# CH552DAPLINK.net
KiCad netlist of a schematic drawn in Altium Designer
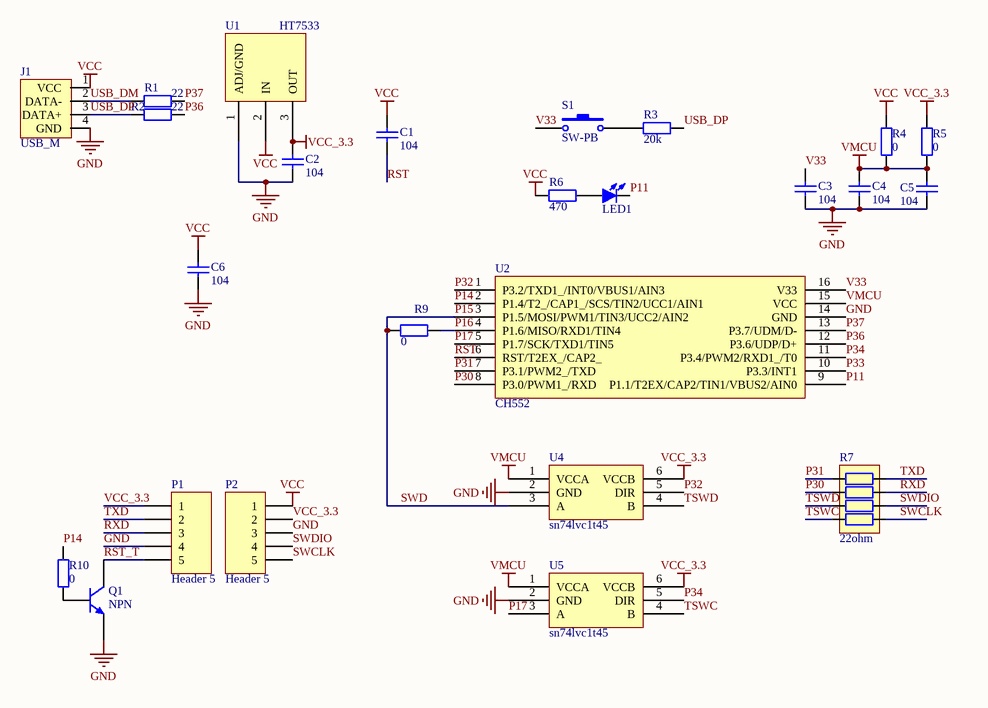
[diagram p0: CH552DAPLINK.SchDoc]

(export (version "E")
  (design (tool "Eeschema 10.0.6"))
  (components
    (comp (ref "C1")
      (value "104")
      (footprint "MY0603_c")
      (description "Capacitor")
      (fields (field (name "Comment") "Cap") (field (name "PUBLISHER") "Altium Limited"))
      (libsource (lib "Miscellaneous Devices") (part "Cap"))
    )
    (comp (ref "C2")
      (value "104")
      (footprint "MY0805_C")
      (description "Capacitor")
      (fields (field (name "Comment") "Cap") (field (name "PUBLISHER") "Altium Limited"))
      (libsource (lib "Miscellaneous Devices") (part "Cap"))
    )
    (comp (ref "C3")
      (value "104")
      (footprint "MY0805_C")
      (description "Capacitor")
      (fields (field (name "Comment") "Cap") (field (name "PUBLISHER") "Altium Limited"))
      (libsource (lib "Miscellaneous Devices") (part "Cap"))
    )
    (comp (ref "C4")
      (value "104")
      (footprint "MY0603_c")
      (description "Capacitor")
      (fields (field (name "Comment") "Cap") (field (name "PUBLISHER") "Altium Limited"))
      (libsource (lib "Miscellaneous Devices") (part "Cap"))
    )
    (comp (ref "C5")
      (value "104")
      (footprint "MY0805_C")
      (description "Capacitor")
      (fields (field (name "Comment") "Cap") (field (name "PUBLISHER") "Altium Limited"))
      (libsource (lib "Miscellaneous Devices") (part "Cap"))
    )
    (comp (ref "C6")
      (value "104")
      (footprint "MY0805_C")
      (description "Capacitor")
      (fields (field (name "Comment") "Cap") (field (name "PUBLISHER") "Altium Limited"))
      (libsource (lib "Miscellaneous Devices") (part "Cap"))
    )
    (comp (ref "J1") (value "USB_M") (footprint "USB_micro_常用") (libsource (lib "SCH封装库") (part "USB_M")))
    (comp (ref "LED1")
      (value "LED-SMD")
      (footprint "MY-0603_LED_B")
      (description "贴片LED")
      (libsource (lib "MY LIB") (part "LED-SMD"))
    )
    (comp (ref "P1")
      (value "Header 5")
      (footprint "header5")
      (description "Header, 5-Pin")
      (fields (field (name "PUBLISHER") "Altium Limited"))
      (libsource (lib "Miscellaneous Connectors") (part "Header 5"))
    )
    (comp (ref "P2")
      (value "Header 5")
      (footprint "header5")
      (description "Header, 5-Pin")
      (fields (field (name "PUBLISHER") "Altium Limited"))
      (libsource (lib "") (part "Header 5_1"))
    )
    (comp (ref "Q1")
      (value "NPN")
      (footprint "MY_SOT23_BJT")
      (description "NPN Bipolar Transistor")
      (fields (field (name "PUBLISHER") "Altium Limited"))
      (libsource (lib "MY BJT&MOS") (part "NPN_SOT23"))
    )
    (comp (ref "R1")
      (value "22")
      (footprint "my0603_R")
      (description "Resistor")
      (fields (field (name "Comment") "Res2") (field (name "PUBLISHER") "Altium Limited"))
      (libsource (lib "") (part "Res2_1"))
    )
    (comp (ref "R2")
      (value "22")
      (footprint "my0603_R")
      (description "Resistor")
      (fields (field (name "Comment") "Res2") (field (name "PUBLISHER") "Altium Limited"))
      (libsource (lib "") (part "Res2_1"))
    )
    (comp (ref "R3")
      (value "20k")
      (footprint "my0603_r")
      (description "Resistor")
      (fields (field (name "Comment") "Res2") (field (name "PUBLISHER") "Altium Limited"))
      (libsource (lib "") (part "Res2_1"))
    )
    (comp (ref "R4")
      (value "0")
      (footprint "my0603_r")
      (description "Resistor")
      (fields (field (name "Comment") "Res2") (field (name "PUBLISHER") "Altium Limited"))
      (libsource (lib "Miscellaneous Devices") (part "Res2"))
    )
    (comp (ref "R5")
      (value "0")
      (footprint "my0603_r")
      (description "Resistor")
      (fields (field (name "Comment") "Res2") (field (name "PUBLISHER") "Altium Limited"))
      (libsource (lib "Miscellaneous Devices") (part "Res2"))
    )
    (comp (ref "R6")
      (value "470")
      (footprint "my0603_r")
      (description "Resistor")
      (fields (field (name "Comment") "Res2") (field (name "PUBLISHER") "Altium Limited"))
      (libsource (lib "") (part "Res2_1"))
    )
    (comp (ref "R7")
      (value "22ohm")
      (footprint "RCA-8P4R-0603")
      (description "贴片网络排阻")
      (fields (field (name "版权归属") "源创客"))
      (libsource (lib "电阻-电容-电感") (part "R-8P4R"))
    )
    (comp (ref "R9")
      (value "0")
      (footprint "my0603_r")
      (description "Resistor")
      (fields (field (name "Comment") "Res2") (field (name "PUBLISHER") "Altium Limited"))
      (libsource (lib "") (part "Res2_3"))
    )
    (comp (ref "R10")
      (value "0")
      (footprint "my0603_r")
      (description "Resistor")
      (fields (field (name "Comment") "Res2") (field (name "PUBLISHER") "Altium Limited"))
      (libsource (lib "") (part "Res2_2"))
    )
    (comp (ref "S1")
      (value "SW-PB")
      (footprint "key_MICRO")
      (description "Switch")
      (fields (field (name "PUBLISHER") "Altium Limited"))
      (libsource (lib "Miscellaneous Devices") (part "SW-PB"))
    )
    (comp (ref "U1")
      (value "HT7533")
      (footprint "MY_SOT-89-3")
      (libsource (lib "MY BJT&MOS") (part "HT7533"))
    )
    (comp (ref "U2") (value "CH552") (footprint "MY-SOP-16_150mil") (libsource (lib "CH552") (part "CH552")))
    (comp (ref "U4")
      (value "sn74lvc1t45")
      (footprint "MY-SOT-23-6")
      (libsource (lib "TMP122") (part "TMP122"))
    )
    (comp (ref "U5")
      (value "sn74lvc1t45")
      (footprint "MY-SOT-23-6")
      (libsource (lib "TMP122") (part "TMP122"))
    )
  )
  (nets
    (net (code "1") (name "/P11") (class "Default")
      (node (ref "LED1") (pin "K") (pinfunction "K_K") (pintype "passive"))
      (node (ref "U2") (pin "9") (pinfunction "P1.1/T2EX/CAP2/TIN1/VBUS2/AIN0_9") (pintype "passive"))
    )
    (net (code "2") (name "/P14") (class "Default")
      (node (ref "R10") (pin "1") (pinfunction "1_1") (pintype "passive"))
      (node (ref "U2") (pin "2") (pinfunction "P1.4/T2_/CAP1_/SCS/TIN2/UCC1/AIN1_2") (pintype "passive"))
    )
    (net (code "3") (name "/P15") (class "Default")
      (node (ref "R9") (pin "2") (pinfunction "2_2") (pintype "passive"))
      (node (ref "U2") (pin "3") (pinfunction "P1.5/MOSI/PWM1/TIN3/UCC2/AIN2_3") (pintype "passive"))
      (node (ref "U4") (pin "3") (pinfunction "A_3") (pintype "passive"))
    )
    (net (code "4") (name "/P16") (class "Default")
      (node (ref "R9") (pin "1") (pinfunction "1_1") (pintype "passive"))
      (node (ref "U2") (pin "4") (pinfunction "P1.6/MISO/RXD1/TIN4_4") (pintype "passive"))
    )
    (net (code "5") (name "/P17") (class "Default")
      (node (ref "U2") (pin "5") (pinfunction "P1.7/SCK/TXD1/TIN5_5") (pintype "passive"))
      (node (ref "U5") (pin "3") (pinfunction "A_3") (pintype "passive"))
    )
    (net (code "6") (name "/P30") (class "Default")
      (node (ref "R7") (pin "7") (pinfunction "7_7") (pintype "passive"))
      (node (ref "U2") (pin "8") (pinfunction "P3.0/PWM1_/RXD_8") (pintype "passive"))
    )
    (net (code "7") (name "/P31") (class "Default")
      (node (ref "R7") (pin "8") (pinfunction "8_8") (pintype "passive"))
      (node (ref "U2") (pin "7") (pinfunction "P3.1/PWM2_/TXD_7") (pintype "passive"))
    )
    (net (code "8") (name "/P32") (class "Default")
      (node (ref "U2") (pin "1") (pinfunction "P3.2/TXD1_/INT0/VBUS1/AIN3_1") (pintype "passive"))
      (node (ref "U4") (pin "5") (pinfunction "DIR_5") (pintype "passive"))
    )
    (net (code "9") (name "/P33") (class "Default")
      (node (ref "U2") (pin "10") (pinfunction "P3.3/INT1_10") (pintype "passive"))
    )
    (net (code "10") (name "/P34") (class "Default")
      (node (ref "U2") (pin "11") (pinfunction "P3.4/PWM2/RXD1_/T0_11") (pintype "passive"))
      (node (ref "U5") (pin "5") (pinfunction "DIR_5") (pintype "passive"))
    )
    (net (code "11") (name "/P36") (class "Default")
      (node (ref "R2") (pin "2") (pinfunction "2_2") (pintype "passive"))
      (node (ref "U2") (pin "12") (pinfunction "P3.6/UDP/D+_12") (pintype "passive"))
    )
    (net (code "12") (name "/P37") (class "Default")
      (node (ref "R1") (pin "2") (pinfunction "2_2") (pintype "passive"))
      (node (ref "U2") (pin "13") (pinfunction "P3.7/UDM/D-_13") (pintype "passive"))
    )
    (net (code "13") (name "/RST") (class "Default")
      (node (ref "C1") (pin "2") (pinfunction "2_2") (pintype "passive"))
      (node (ref "U2") (pin "6") (pinfunction "RST/T2EX_/CAP2__6") (pintype "passive"))
    )
    (net (code "14") (name "/RST_T") (class "Default")
      (node (ref "P1") (pin "5") (pinfunction "5_5") (pintype "passive"))
      (node (ref "Q1") (pin "3") (pinfunction "C_3") (pintype "passive"))
    )
    (net (code "15") (name "/RXD") (class "Default")
      (node (ref "P1") (pin "3") (pinfunction "3_3") (pintype "passive"))
      (node (ref "R7") (pin "2") (pinfunction "2_2") (pintype "passive"))
    )
    (net (code "16") (name "/SWCLK") (class "Default")
      (node (ref "P2") (pin "5") (pinfunction "5_5") (pintype "passive"))
      (node (ref "R7") (pin "4") (pinfunction "4_4") (pintype "passive"))
    )
    (net (code "17") (name "/SWDIO") (class "Default")
      (node (ref "P2") (pin "4") (pinfunction "4_4") (pintype "passive"))
      (node (ref "R7") (pin "3") (pinfunction "3_3") (pintype "passive"))
    )
    (net (code "18") (name "/TSWC") (class "Default")
      (node (ref "R7") (pin "5") (pinfunction "5_5") (pintype "passive"))
      (node (ref "U5") (pin "4") (pinfunction "B_4") (pintype "passive"))
    )
    (net (code "19") (name "/TSWD") (class "Default")
      (node (ref "R7") (pin "6") (pinfunction "6_6") (pintype "passive"))
      (node (ref "U4") (pin "4") (pinfunction "B_4") (pintype "passive"))
    )
    (net (code "20") (name "/TXD") (class "Default")
      (node (ref "P1") (pin "2") (pinfunction "2_2") (pintype "passive"))
      (node (ref "R7") (pin "1") (pinfunction "1_1") (pintype "passive"))
    )
    (net (code "21") (name "/USB_DM") (class "Default")
      (node (ref "J1") (pin "2") (pinfunction "DATA-_2") (pintype "passive"))
      (node (ref "R1") (pin "1") (pinfunction "1_1") (pintype "passive"))
    )
    (net (code "22") (name "/USB_DP") (class "Default")
      (node (ref "J1") (pin "3") (pinfunction "DATA+_3") (pintype "passive"))
      (node (ref "R2") (pin "1") (pinfunction "1_1") (pintype "passive"))
      (node (ref "R3") (pin "2") (pinfunction "2_2") (pintype "passive"))
    )
    (net (code "23") (name "/V33") (class "Default")
      (node (ref "C3") (pin "1") (pinfunction "1_1") (pintype "passive"))
      (node (ref "S1") (pin "1") (pinfunction "1_1") (pintype "passive"))
      (node (ref "U2") (pin "16") (pinfunction "V33_16") (pintype "passive"))
    )
    (net (code "24") (name "GND") (class "Default")
      (node (ref "C2") (pin "2") (pinfunction "2_2") (pintype "passive"))
      (node (ref "C3") (pin "2") (pinfunction "2_2") (pintype "passive"))
      (node (ref "C4") (pin "2") (pinfunction "2_2") (pintype "passive"))
      (node (ref "C5") (pin "2") (pinfunction "2_2") (pintype "passive"))
      (node (ref "C6") (pin "2") (pinfunction "2_2") (pintype "passive"))
      (node (ref "J1") (pin "4") (pinfunction "GND_4") (pintype "passive"))
      (node (ref "P1") (pin "4") (pinfunction "4_4") (pintype "passive"))
      (node (ref "P2") (pin "3") (pinfunction "3_3") (pintype "passive"))
      (node (ref "Q1") (pin "2") (pinfunction "E_2") (pintype "passive"))
      (node (ref "U1") (pin "1") (pinfunction "ADJ/GND_1") (pintype "passive"))
      (node (ref "U2") (pin "14") (pinfunction "GND_14") (pintype "passive"))
      (node (ref "U4") (pin "2") (pinfunction "GND_2") (pintype "passive"))
      (node (ref "U5") (pin "2") (pinfunction "GND_2") (pintype "passive"))
    )
    (net (code "25") (name "Net-(LED1-PadA)") (class "Default")
      (node (ref "LED1") (pin "A") (pinfunction "A_A") (pintype "passive"))
      (node (ref "R6") (pin "2") (pinfunction "2_2") (pintype "passive"))
    )
    (net (code "26") (name "Net-(Q1-B)") (class "Default")
      (node (ref "Q1") (pin "1") (pinfunction "B_1") (pintype "passive"))
      (node (ref "R10") (pin "2") (pinfunction "2_2") (pintype "passive"))
    )
    (net (code "27") (name "Net-(R3-Pad1)") (class "Default")
      (node (ref "R3") (pin "1") (pinfunction "1_1") (pintype "passive"))
      (node (ref "S1") (pin "2") (pinfunction "2_2") (pintype "passive"))
    )
    (net (code "28") (name "VCC") (class "Default")
      (node (ref "C1") (pin "1") (pinfunction "1_1") (pintype "passive"))
      (node (ref "C6") (pin "1") (pinfunction "1_1") (pintype "passive"))
      (node (ref "J1") (pin "1") (pinfunction "VCC_1") (pintype "passive"))
      (node (ref "P2") (pin "1") (pinfunction "1_1") (pintype "passive"))
      (node (ref "R4") (pin "2") (pinfunction "2_2") (pintype "passive"))
      (node (ref "R6") (pin "1") (pinfunction "1_1") (pintype "passive"))
      (node (ref "U1") (pin "2") (pinfunction "IN_2") (pintype "passive"))
    )
    (net (code "29") (name "VCC_3.3") (class "Default")
      (node (ref "C2") (pin "1") (pinfunction "1_1") (pintype "passive"))
      (node (ref "P1") (pin "1") (pinfunction "1_1") (pintype "passive"))
      (node (ref "P2") (pin "2") (pinfunction "2_2") (pintype "passive"))
      (node (ref "R5") (pin "2") (pinfunction "2_2") (pintype "passive"))
      (node (ref "U1") (pin "3") (pinfunction "OUT_3") (pintype "passive"))
      (node (ref "U4") (pin "6") (pinfunction "VCCB_6") (pintype "passive"))
      (node (ref "U5") (pin "6") (pinfunction "VCCB_6") (pintype "passive"))
    )
    (net (code "30") (name "VMCU") (class "Default")
      (node (ref "C4") (pin "1") (pinfunction "1_1") (pintype "passive"))
      (node (ref "C5") (pin "1") (pinfunction "1_1") (pintype "passive"))
      (node (ref "R4") (pin "1") (pinfunction "1_1") (pintype "passive"))
      (node (ref "R5") (pin "1") (pinfunction "1_1") (pintype "passive"))
      (node (ref "U2") (pin "15") (pinfunction "VCC_15") (pintype "passive"))
      (node (ref "U4") (pin "1") (pinfunction "VCCA_1") (pintype "passive"))
      (node (ref "U5") (pin "1") (pinfunction "VCCA_1") (pintype "passive"))
    )
  )
)
